# Sensor_Board_2_01_HX711_DS18b2.net
KiCad netlist of a schematic drawn in EAGLE
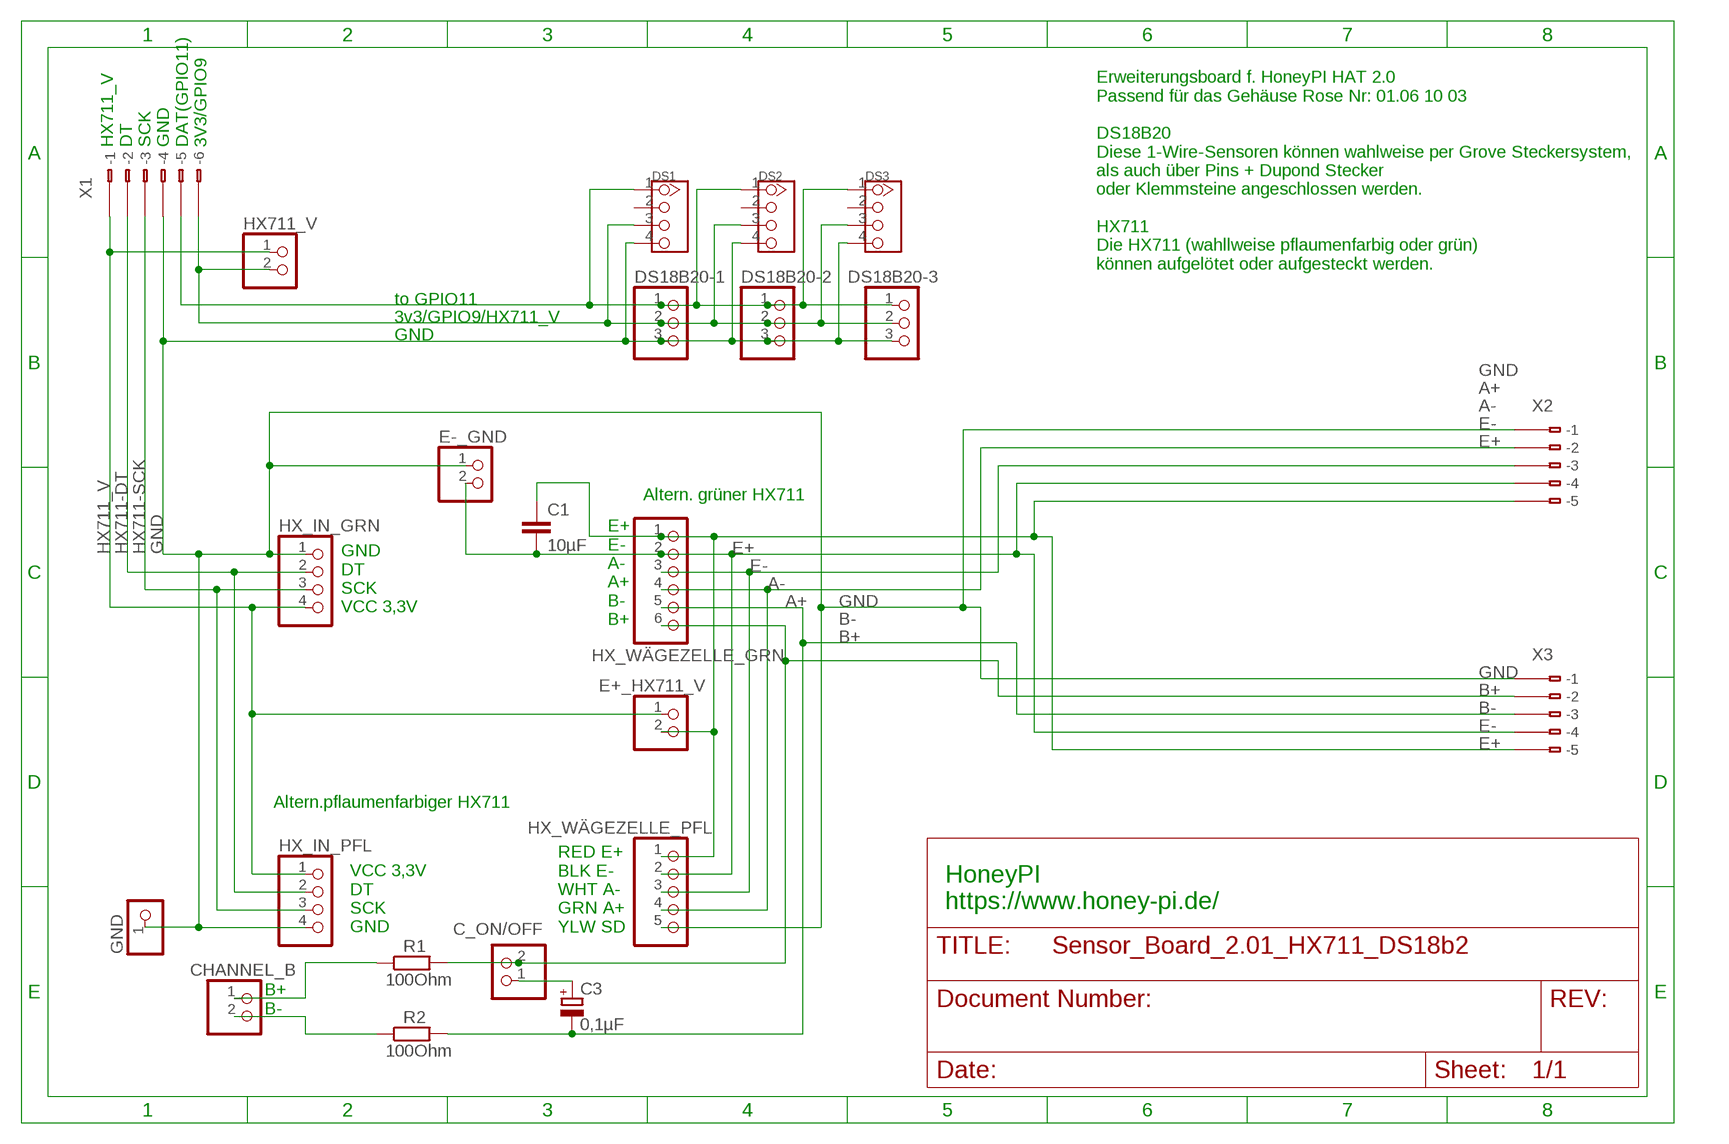
[diagram p0: schematic, sheet 1]

(export (version "E")
  (design (tool "Eeschema 10.0.6"))
  (components
    (comp (ref "C1")
      (value "10µF")
      (footprint "eagle-import:C5B2.5")
      (libsource (lib "eagle-import") (part "C5/2.5"))
    )
    (comp (ref "C3")
      (value "0,1µF")
      (footprint "eagle-import:E2,5-7")
      (libsource (lib "eagle-import") (part "CPOL-EUE2.5-7"))
    )
    (comp (ref "CHANNEL_B")
      (value "PINHD-1X2")
      (footprint "eagle-import:1X02")
      (libsource (lib "eagle-import") (part "PINHD-1X2"))
    )
    (comp (ref "C_ON/OFF")
      (value "PINHD-1X2")
      (footprint "eagle-import:1X02")
      (libsource (lib "eagle-import") (part "PINHD-1X2"))
    )
    (comp (ref "DS1")
      (value "TWIG-4P-2.0-2.0")
      (footprint "eagle-import:4P-2.0")
      (libsource (lib "eagle-import") (part "TWIG-4P-2.0-2.0"))
    )
    (comp (ref "DS2")
      (value "TWIG-4P-2.0-2.0")
      (footprint "eagle-import:4P-2.0")
      (libsource (lib "eagle-import") (part "TWIG-4P-2.0-2.0"))
    )
    (comp (ref "DS3")
      (value "TWIG-4P-2.0-2.0")
      (footprint "eagle-import:4P-2.0")
      (libsource (lib "eagle-import") (part "TWIG-4P-2.0-2.0"))
    )
    (comp (ref "DS18B20-1")
      (value "PINHD-1X3")
      (footprint "eagle-import:1X03")
      (libsource (lib "eagle-import") (part "PINHD-1X3"))
    )
    (comp (ref "DS18B20-2")
      (value "PINHD-1X3")
      (footprint "eagle-import:1X03")
      (libsource (lib "eagle-import") (part "PINHD-1X3"))
    )
    (comp (ref "DS18B20-3")
      (value "PINHD-1X3")
      (footprint "eagle-import:1X03")
      (libsource (lib "eagle-import") (part "PINHD-1X3"))
    )
    (comp (ref "E+_HX711_V")
      (value "PINHD-1X2")
      (footprint "eagle-import:1X02")
      (libsource (lib "eagle-import") (part "PINHD-1X2"))
    )
    (comp (ref "E-_GND")
      (value "PINHD-1X2")
      (footprint "eagle-import:1X02")
      (libsource (lib "eagle-import") (part "PINHD-1X2"))
    )
    (comp (ref "GND")
      (value "PINHD-1X1")
      (footprint "eagle-import:1X01")
      (libsource (lib "eagle-import") (part "PINHD-1X1"))
    )
    (comp (ref "HX711_V")
      (value "PINHD-1X2")
      (footprint "eagle-import:1X02")
      (libsource (lib "eagle-import") (part "PINHD-1X2"))
    )
    (comp (ref "HX_IN_GRN")
      (value "PINHD-1X4")
      (footprint "eagle-import:1X04")
      (libsource (lib "eagle-import") (part "PINHD-1X4"))
    )
    (comp (ref "HX_IN_PFL")
      (value "PINHD-1X4")
      (footprint "eagle-import:1X04")
      (libsource (lib "eagle-import") (part "PINHD-1X4"))
    )
    (comp (ref "HX_WÄGEZELLE_GRN")
      (value "PINHD-1X6")
      (footprint "eagle-import:1X06")
      (libsource (lib "eagle-import") (part "PINHD-1X6"))
    )
    (comp (ref "HX_WÄGEZELLE_PFL")
      (value "PINHD-1X5")
      (footprint "eagle-import:1X05")
      (libsource (lib "eagle-import") (part "PINHD-1X5"))
    )
    (comp (ref "R1")
      (value "100Ohm")
      (footprint "eagle-import:0207_10")
      (libsource (lib "eagle-import") (part "R-EU_0207/10"))
    )
    (comp (ref "R2")
      (value "100Ohm")
      (footprint "eagle-import:0207_10")
      (libsource (lib "eagle-import") (part "R-EU_0207/10"))
    )
    (comp (ref "X1")
      (value "233-506")
      (footprint "eagle-import:233-506")
      (fields (field (name "MF") "Wago Corporation") (field (name "MPN") "0233-0506"))
      (libsource (lib "eagle-import") (part "233-506"))
    )
    (comp (ref "X2")
      (value "233-505")
      (footprint "eagle-import:233-505")
      (fields (field (name "MF") "Wago Corporation") (field (name "MPN") "0233-0505"))
      (libsource (lib "eagle-import") (part "233-505"))
    )
    (comp (ref "X3")
      (value "233-505")
      (footprint "eagle-import:233-505")
      (fields (field (name "MF") "Wago Corporation") (field (name "MPN") "0233-0505"))
      (libsource (lib "eagle-import") (part "233-505"))
    )
  )
  (nets
    (net (code "1") (name "/A+") (class "Default")
      (node (ref "HX_WÄGEZELLE_GRN") (pin "4") (pinfunction "4_4") (pintype "passive"))
      (node (ref "HX_WÄGEZELLE_PFL") (pin "4") (pinfunction "4_4") (pintype "passive"))
      (node (ref "X2") (pin "B2") (pinfunction "B-2_B2") (pintype "passive"))
    )
    (net (code "2") (name "/A-") (class "Default")
      (node (ref "HX_WÄGEZELLE_GRN") (pin "3") (pinfunction "3_3") (pintype "passive"))
      (node (ref "HX_WÄGEZELLE_PFL") (pin "3") (pinfunction "3_3") (pintype "passive"))
      (node (ref "X2") (pin "B3") (pinfunction "B-3_B3") (pintype "passive"))
    )
    (net (code "3") (name "/B+") (class "Default")
      (node (ref "C_ON/OFF") (pin "2") (pinfunction "2_2") (pintype "passive"))
      (node (ref "HX_WÄGEZELLE_GRN") (pin "6") (pinfunction "6_6") (pintype "passive"))
      (node (ref "R1") (pin "2") (pinfunction "2_2") (pintype "passive"))
      (node (ref "X3") (pin "B2") (pinfunction "B-2_B2") (pintype "passive"))
    )
    (net (code "4") (name "/B-") (class "Default")
      (node (ref "C3") (pin "-") (pinfunction "-_-") (pintype "passive"))
      (node (ref "HX_WÄGEZELLE_GRN") (pin "5") (pinfunction "5_5") (pintype "passive"))
      (node (ref "R2") (pin "2") (pinfunction "2_2") (pintype "passive"))
      (node (ref "X3") (pin "B3") (pinfunction "B-3_B3") (pintype "passive"))
    )
    (net (code "5") (name "/E+") (class "Default")
      (node (ref "C1") (pin "1") (pinfunction "1_1") (pintype "passive"))
      (node (ref "E+_HX711_V") (pin "2") (pinfunction "2_2") (pintype "passive"))
      (node (ref "HX_WÄGEZELLE_GRN") (pin "1") (pinfunction "1_1") (pintype "passive"))
      (node (ref "HX_WÄGEZELLE_PFL") (pin "1") (pinfunction "1_1") (pintype "passive"))
      (node (ref "X2") (pin "B5") (pinfunction "B-5_B5") (pintype "passive"))
      (node (ref "X3") (pin "B5") (pinfunction "B-5_B5") (pintype "passive"))
    )
    (net (code "6") (name "/E-") (class "Default")
      (node (ref "C1") (pin "2") (pinfunction "2_2") (pintype "passive"))
      (node (ref "E-_GND") (pin "2") (pinfunction "2_2") (pintype "passive"))
      (node (ref "HX_WÄGEZELLE_GRN") (pin "2") (pinfunction "2_2") (pintype "passive"))
      (node (ref "HX_WÄGEZELLE_PFL") (pin "2") (pinfunction "2_2") (pintype "passive"))
      (node (ref "X2") (pin "B4") (pinfunction "B-4_B4") (pintype "passive"))
      (node (ref "X3") (pin "B4") (pinfunction "B-4_B4") (pintype "passive"))
    )
    (net (code "7") (name "/GND") (class "Default")
      (node (ref "DS1") (pin "4") (pinfunction "4_4") (pintype "bidirectional"))
      (node (ref "DS18B20-1") (pin "3") (pinfunction "3_3") (pintype "passive"))
      (node (ref "DS18B20-2") (pin "3") (pinfunction "3_3") (pintype "passive"))
      (node (ref "DS18B20-3") (pin "3") (pinfunction "3_3") (pintype "passive"))
      (node (ref "DS2") (pin "4") (pinfunction "4_4") (pintype "bidirectional"))
      (node (ref "DS3") (pin "4") (pinfunction "4_4") (pintype "bidirectional"))
      (node (ref "E-_GND") (pin "1") (pinfunction "1_1") (pintype "passive"))
      (node (ref "GND") (pin "1") (pinfunction "1_1") (pintype "passive"))
      (node (ref "HX_IN_GRN") (pin "1") (pinfunction "1_1") (pintype "passive"))
      (node (ref "HX_IN_PFL") (pin "4") (pinfunction "4_4") (pintype "passive"))
      (node (ref "HX_WÄGEZELLE_PFL") (pin "5") (pinfunction "5_5") (pintype "passive"))
      (node (ref "X1") (pin "B4") (pinfunction "B-4_B4") (pintype "passive"))
      (node (ref "X2") (pin "B1") (pinfunction "B-1_B1") (pintype "passive"))
      (node (ref "X3") (pin "B1") (pinfunction "B-1_B1") (pintype "passive"))
    )
    (net (code "8") (name "/HX711-DT") (class "Default")
      (node (ref "HX_IN_GRN") (pin "2") (pinfunction "2_2") (pintype "passive"))
      (node (ref "HX_IN_PFL") (pin "2") (pinfunction "2_2") (pintype "passive"))
      (node (ref "X1") (pin "B2") (pinfunction "B-2_B2") (pintype "passive"))
    )
    (net (code "9") (name "/HX711-SCK") (class "Default")
      (node (ref "HX_IN_GRN") (pin "3") (pinfunction "3_3") (pintype "passive"))
      (node (ref "HX_IN_PFL") (pin "3") (pinfunction "3_3") (pintype "passive"))
      (node (ref "X1") (pin "B3") (pinfunction "B-3_B3") (pintype "passive"))
    )
    (net (code "10") (name "/HX711_V") (class "Default")
      (node (ref "E+_HX711_V") (pin "1") (pinfunction "1_1") (pintype "passive"))
      (node (ref "HX711_V") (pin "1") (pinfunction "1_1") (pintype "passive"))
      (node (ref "HX_IN_GRN") (pin "4") (pinfunction "4_4") (pintype "passive"))
      (node (ref "HX_IN_PFL") (pin "1") (pinfunction "1_1") (pintype "passive"))
      (node (ref "X1") (pin "B1") (pinfunction "B-1_B1") (pintype "passive"))
    )
    (net (code "11") (name "Net-(C3-Pad+)") (class "Default")
      (node (ref "C3") (pin "+") (pinfunction "+_+") (pintype "passive"))
      (node (ref "C_ON/OFF") (pin "1") (pinfunction "1_1") (pintype "passive"))
    )
    (net (code "12") (name "Net-(CHANNEL_B-Pad1)") (class "Default")
      (node (ref "CHANNEL_B") (pin "1") (pinfunction "1_1") (pintype "passive"))
      (node (ref "R1") (pin "1") (pinfunction "1_1") (pintype "passive"))
    )
    (net (code "13") (name "Net-(CHANNEL_B-Pad2)") (class "Default")
      (node (ref "CHANNEL_B") (pin "2") (pinfunction "2_2") (pintype "passive"))
      (node (ref "R2") (pin "1") (pinfunction "1_1") (pintype "passive"))
    )
    (net (code "14") (name "Net-(X1-B-5)") (class "Default")
      (node (ref "DS1") (pin "1") (pinfunction "1_1") (pintype "bidirectional"))
      (node (ref "DS18B20-1") (pin "1") (pinfunction "1_1") (pintype "passive"))
      (node (ref "DS18B20-2") (pin "1") (pinfunction "1_1") (pintype "passive"))
      (node (ref "DS18B20-3") (pin "1") (pinfunction "1_1") (pintype "passive"))
      (node (ref "DS2") (pin "1") (pinfunction "1_1") (pintype "bidirectional"))
      (node (ref "DS3") (pin "1") (pinfunction "1_1") (pintype "bidirectional"))
      (node (ref "X1") (pin "B5") (pinfunction "B-5_B5") (pintype "passive"))
    )
    (net (code "15") (name "Net-(X1-B-6)") (class "Default")
      (node (ref "DS1") (pin "3") (pinfunction "3_3") (pintype "bidirectional"))
      (node (ref "DS18B20-1") (pin "2") (pinfunction "2_2") (pintype "passive"))
      (node (ref "DS18B20-2") (pin "2") (pinfunction "2_2") (pintype "passive"))
      (node (ref "DS18B20-3") (pin "2") (pinfunction "2_2") (pintype "passive"))
      (node (ref "DS2") (pin "3") (pinfunction "3_3") (pintype "bidirectional"))
      (node (ref "DS3") (pin "3") (pinfunction "3_3") (pintype "bidirectional"))
      (node (ref "HX711_V") (pin "2") (pinfunction "2_2") (pintype "passive"))
      (node (ref "X1") (pin "B6") (pinfunction "B-6_B6") (pintype "passive"))
    )
    (net (code "16") (name "unconnected-(DS1-Pad2)") (class "Default")
      (node (ref "DS1") (pin "2") (pinfunction "2_2") (pintype "bidirectional"))
    )
    (net (code "17") (name "unconnected-(DS2-Pad2)") (class "Default")
      (node (ref "DS2") (pin "2") (pinfunction "2_2") (pintype "bidirectional"))
    )
    (net (code "18") (name "unconnected-(DS3-Pad2)") (class "Default")
      (node (ref "DS3") (pin "2") (pinfunction "2_2") (pintype "bidirectional"))
    )
    (net (code "19") (name "unconnected-(X1--1-PadA1)") (class "Default")
      (node (ref "X1") (pin "A1") (pinfunction "-1_A1") (pintype "passive"))
    )
    (net (code "20") (name "unconnected-(X1--2-PadA2)") (class "Default")
      (node (ref "X1") (pin "A2") (pinfunction "-2_A2") (pintype "passive"))
    )
    (net (code "21") (name "unconnected-(X1--3-PadA3)") (class "Default")
      (node (ref "X1") (pin "A3") (pinfunction "-3_A3") (pintype "passive"))
    )
    (net (code "22") (name "unconnected-(X1--4-PadA4)") (class "Default")
      (node (ref "X1") (pin "A4") (pinfunction "-4_A4") (pintype "passive"))
    )
    (net (code "23") (name "unconnected-(X1--5-PadA5)") (class "Default")
      (node (ref "X1") (pin "A5") (pinfunction "-5_A5") (pintype "passive"))
    )
    (net (code "24") (name "unconnected-(X1--6-PadA6)") (class "Default")
      (node (ref "X1") (pin "A6") (pinfunction "-6_A6") (pintype "passive"))
    )
    (net (code "25") (name "unconnected-(X2--1-PadA1)") (class "Default")
      (node (ref "X2") (pin "A1") (pinfunction "-1_A1") (pintype "passive"))
    )
    (net (code "26") (name "unconnected-(X2--2-PadA2)") (class "Default")
      (node (ref "X2") (pin "A2") (pinfunction "-2_A2") (pintype "passive"))
    )
    (net (code "27") (name "unconnected-(X2--3-PadA3)") (class "Default")
      (node (ref "X2") (pin "A3") (pinfunction "-3_A3") (pintype "passive"))
    )
    (net (code "28") (name "unconnected-(X2--4-PadA4)") (class "Default")
      (node (ref "X2") (pin "A4") (pinfunction "-4_A4") (pintype "passive"))
    )
    (net (code "29") (name "unconnected-(X2--5-PadA5)") (class "Default")
      (node (ref "X2") (pin "A5") (pinfunction "-5_A5") (pintype "passive"))
    )
    (net (code "30") (name "unconnected-(X3--1-PadA1)") (class "Default")
      (node (ref "X3") (pin "A1") (pinfunction "-1_A1") (pintype "passive"))
    )
    (net (code "31") (name "unconnected-(X3--2-PadA2)") (class "Default")
      (node (ref "X3") (pin "A2") (pinfunction "-2_A2") (pintype "passive"))
    )
    (net (code "32") (name "unconnected-(X3--3-PadA3)") (class "Default")
      (node (ref "X3") (pin "A3") (pinfunction "-3_A3") (pintype "passive"))
    )
    (net (code "33") (name "unconnected-(X3--4-PadA4)") (class "Default")
      (node (ref "X3") (pin "A4") (pinfunction "-4_A4") (pintype "passive"))
    )
    (net (code "34") (name "unconnected-(X3--5-PadA5)") (class "Default")
      (node (ref "X3") (pin "A5") (pinfunction "-5_A5") (pintype "passive"))
    )
  )
)
